# SCH_ECE198-04.net
KiCad netlist of a schematic drawn in EasyEDA
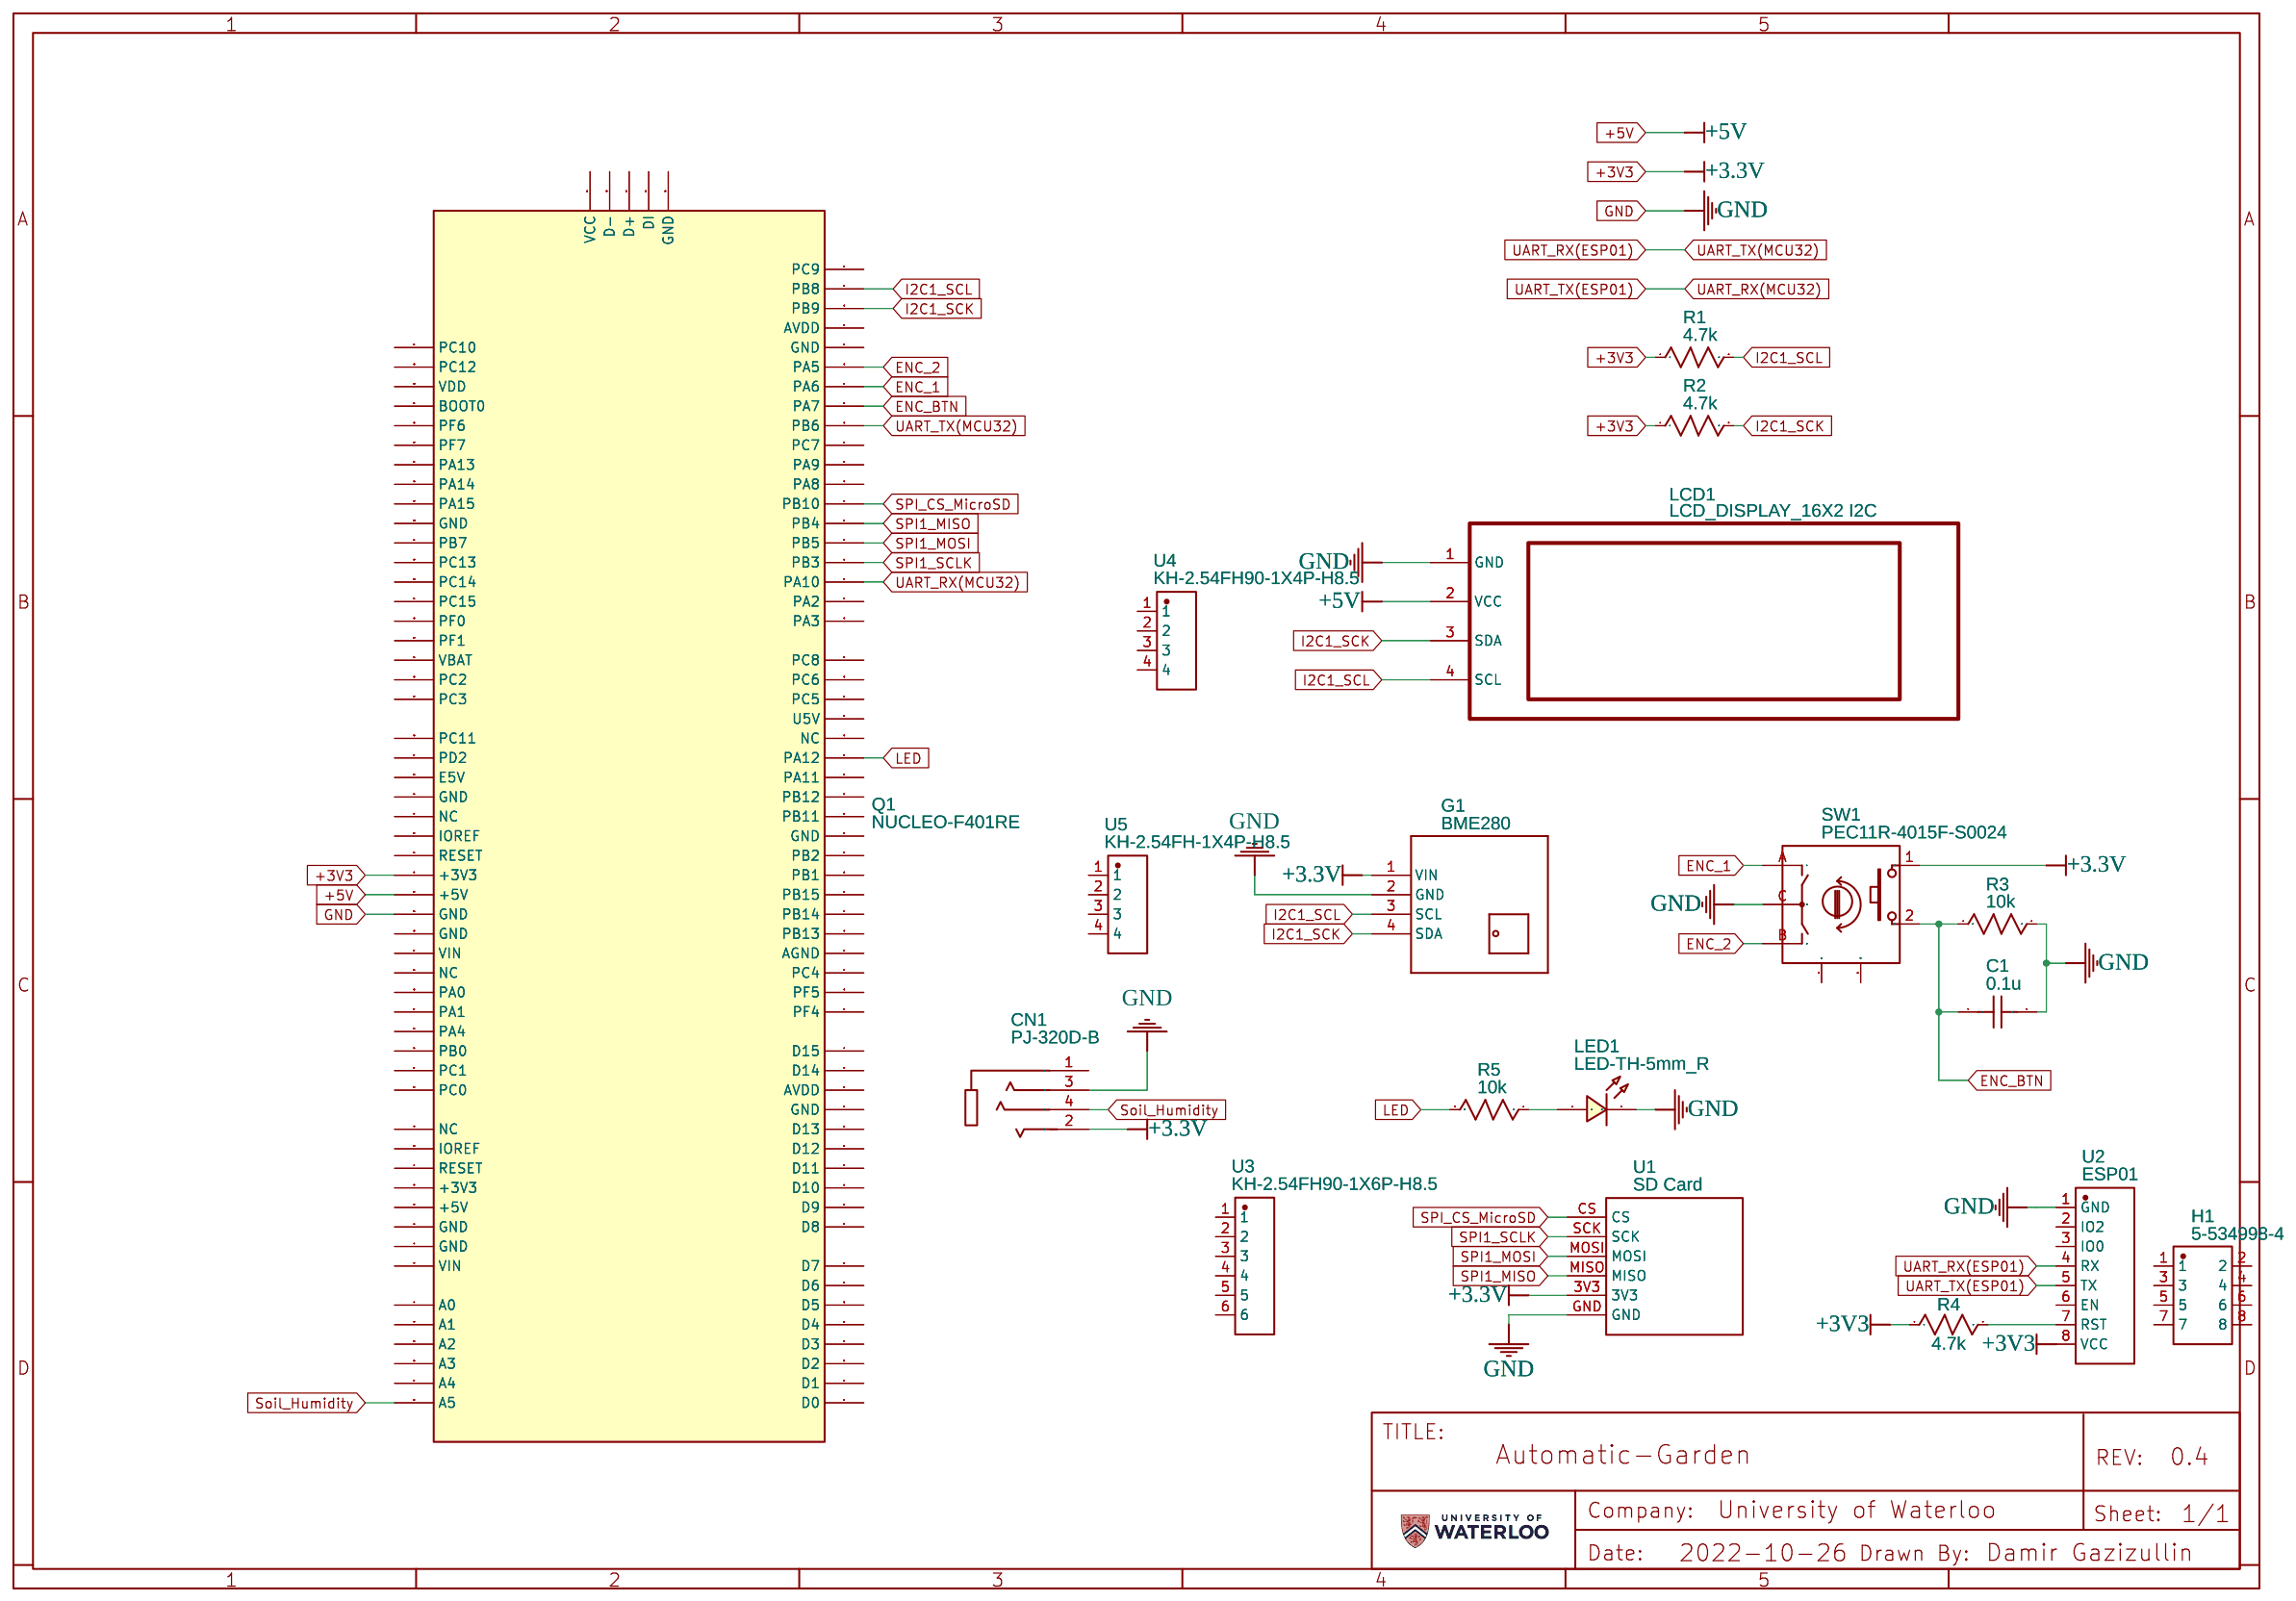
[diagram p0: schematic sheet]

(export (version "E")
  (design (tool "Eeschema 10.0.6"))
  (components
    (comp (ref "C1") (value "0.1u") (libsource (lib "") (part "C_0603_US")))
    (comp (ref "CN1")
      (value "PJ-320D-B")
      (fields (field (name "BOM_Supplier Part") "C2884940"))
      (libsource (lib "") (part "PJ-320D-B"))
    )
    (comp (ref "G1") (value "BME280") (libsource (lib "") (part "TEMP-HUM-PRES-BME280")))
    (comp (ref "H1")
      (value "5-534998-4")
      (fields (field (name "BOM_Supplier Part") "C404201"))
      (libsource (lib "") (part "5-534998-4"))
    )
    (comp (ref "LCD1") (value "LCD_DISPLAY_16X2 I2C") (libsource (lib "") (part "LCD_DISPLAY_16X2 I2C")))
    (comp (ref "LED1")
      (value "LED-TH-5mm_R")
      (fields
        (field (name "BOM_Manufacturer Part") "333-2SURD/S530-A3")
        (field (name "BOM_Supplier Part") "C87271")
      )
      (libsource (lib "") (part "LED-TH-5mm_R"))
    )
    (comp (ref "Q1") (value "NUCLEO-F401RE") (libsource (lib "") (part "NUCLEO-F401RE")))
    (comp (ref "R1") (value "4.7k") (libsource (lib "") (part "R_0603_US")))
    (comp (ref "R2") (value "4.7k") (libsource (lib "") (part "R_0603_US")))
    (comp (ref "R3") (value "10k") (libsource (lib "") (part "R_AXIAL-0.5_US")))
    (comp (ref "R4") (value "4.7k") (libsource (lib "") (part "R_AXIAL-0.5_US")))
    (comp (ref "R5") (value "10k") (libsource (lib "") (part "R_AXIAL-0.5_US_1")))
    (comp (ref "SW1")
      (value "PEC11R-4015F-S0024")
      (fields (field (name "BOM_Supplier Part") "C143789"))
      (libsource (lib "") (part "PEC11R-4015F-S0024"))
    )
    (comp (ref "U1") (value "SD Card") (libsource (lib "") (part "SD Card")))
    (comp (ref "U2") (value "ESP01") (libsource (lib "") (part "ESP01")))
    (comp (ref "U3")
      (value "KH-2.54FH90-1X6P-H8.5")
      (fields (field (name "BOM_Supplier Part") "C2932681"))
      (libsource (lib "") (part "KH-2.54FH90-1X6P-H8.5"))
    )
    (comp (ref "U4")
      (value "KH-2.54FH90-1X4P-H8.5")
      (fields (field (name "BOM_Supplier Part") "C2932680"))
      (libsource (lib "") (part "KH-2.54FH90-1X4P-H8.5"))
    )
    (comp (ref "U5")
      (value "KH-2.54FH-1X4P-H8.5")
      (fields (field (name "BOM_Supplier Part") "C2905415"))
      (libsource (lib "") (part "KH-2.54FH-1X4P-H8.5"))
    )
  )
  (nets
    (net (code "1") (name "+3V3") (class "Default")
      (node (ref "CN1") (pin "2") (pinfunction "2_2") (pintype "unspecified"))
      (node (ref "G1") (pin "1") (pinfunction "VIN_1") (pintype "bidirectional"))
      (node (ref "Q1") (pin "91") (pinfunction "+3V3_91") (pintype "unspecified"))
      (node (ref "R1") (pin "1") (pinfunction "1_1") (pintype "unspecified"))
      (node (ref "R2") (pin "1") (pinfunction "1_1") (pintype "unspecified"))
      (node (ref "R4") (pin "1") (pinfunction "1_1") (pintype "unspecified"))
      (node (ref "SW1") (pin "1") (pinfunction "1_1") (pintype "unspecified"))
      (node (ref "U1") (pin "3V3") (pinfunction "3V3_3V3") (pintype "unspecified"))
      (node (ref "U2") (pin "8") (pinfunction "VCC_8") (pintype "unspecified"))
    )
    (net (code "2") (name "+5V") (class "Default")
      (node (ref "LCD1") (pin "2") (pinfunction "VCC_2") (pintype "passive"))
      (node (ref "Q1") (pin "90") (pinfunction "+5V_90") (pintype "unspecified"))
    )
    (net (code "3") (name "ENC_1") (class "Default")
      (node (ref "Q1") (pin "14") (pinfunction "PA6_14") (pintype "bidirectional"))
      (node (ref "SW1") (pin "A") (pinfunction "A_A") (pintype "unspecified"))
    )
    (net (code "4") (name "ENC_2") (class "Default")
      (node (ref "Q1") (pin "13") (pinfunction "PA5_13") (pintype "bidirectional"))
      (node (ref "SW1") (pin "B") (pinfunction "B_B") (pintype "unspecified"))
    )
    (net (code "5") (name "ENC_BTN") (class "Default")
      (node (ref "C1") (pin "1") (pinfunction "1_1") (pintype "unspecified"))
      (node (ref "Q1") (pin "15") (pinfunction "PA7_15") (pintype "bidirectional"))
      (node (ref "R3") (pin "1") (pinfunction "1_1") (pintype "unspecified"))
      (node (ref "SW1") (pin "2") (pinfunction "2_2") (pintype "unspecified"))
    )
    (net (code "6") (name "GND") (class "Default")
      (node (ref "C1") (pin "2") (pinfunction "2_2") (pintype "unspecified"))
      (node (ref "CN1") (pin "3") (pinfunction "3_3") (pintype "unspecified"))
      (node (ref "G1") (pin "2") (pinfunction "GND_2") (pintype "bidirectional"))
      (node (ref "LCD1") (pin "1") (pinfunction "GND_1") (pintype "passive"))
      (node (ref "LED1") (pin "2") (pinfunction "2_2") (pintype "unspecified"))
      (node (ref "Q1") (pin "89") (pinfunction "GND_89") (pintype "unspecified"))
      (node (ref "R3") (pin "2") (pinfunction "2_2") (pintype "unspecified"))
      (node (ref "SW1") (pin "C") (pinfunction "C_C") (pintype "unspecified"))
      (node (ref "U1") (pin "GND") (pinfunction "GND_GND") (pintype "unspecified"))
      (node (ref "U2") (pin "1") (pinfunction "GND_1") (pintype "unspecified"))
    )
    (net (code "7") (name "I2C1_SCK") (class "Default")
      (node (ref "G1") (pin "4") (pinfunction "SDA_4") (pintype "bidirectional"))
      (node (ref "LCD1") (pin "3") (pinfunction "SDA_3") (pintype "passive"))
      (node (ref "Q1") (pin "10") (pinfunction "PB9_10") (pintype "bidirectional"))
      (node (ref "R2") (pin "2") (pinfunction "2_2") (pintype "unspecified"))
    )
    (net (code "8") (name "I2C1_SCL") (class "Default")
      (node (ref "G1") (pin "3") (pinfunction "SCL_3") (pintype "bidirectional"))
      (node (ref "LCD1") (pin "4") (pinfunction "SCL_4") (pintype "passive"))
      (node (ref "Q1") (pin "9") (pinfunction "PB8_9") (pintype "bidirectional"))
      (node (ref "R1") (pin "2") (pinfunction "2_2") (pintype "unspecified"))
    )
    (net (code "9") (name "LED") (class "Default")
      (node (ref "Q1") (pin "33") (pinfunction "PA12_33") (pintype "bidirectional"))
      (node (ref "R5") (pin "2") (pinfunction "2_2") (pintype "unspecified"))
    )
    (net (code "10") (name "Net-(LED1-Pad1)") (class "Default")
      (node (ref "LED1") (pin "1") (pinfunction "1_1") (pintype "unspecified"))
      (node (ref "R5") (pin "1") (pinfunction "1_1") (pintype "unspecified"))
    )
    (net (code "11") (name "Net-(U2-RST)") (class "Default")
      (node (ref "R4") (pin "2") (pinfunction "2_2") (pintype "unspecified"))
      (node (ref "U2") (pin "7") (pinfunction "RST_7") (pintype "unspecified"))
    )
    (net (code "12") (name "SPI1_MISO") (class "Default")
      (node (ref "Q1") (pin "21") (pinfunction "PB4_21") (pintype "bidirectional"))
      (node (ref "U1") (pin "MISO") (pinfunction "MISO_MISO") (pintype "unspecified"))
    )
    (net (code "13") (name "SPI1_MOSI") (class "Default")
      (node (ref "Q1") (pin "22") (pinfunction "PB5_22") (pintype "bidirectional"))
      (node (ref "U1") (pin "MOSI") (pinfunction "MOSI_MOSI") (pintype "unspecified"))
    )
    (net (code "14") (name "SPI1_SCLK") (class "Default")
      (node (ref "Q1") (pin "23") (pinfunction "PB3_23") (pintype "bidirectional"))
      (node (ref "U1") (pin "SCK") (pinfunction "SCK_SCK") (pintype "unspecified"))
    )
    (net (code "15") (name "SPI_CS_MicroSD") (class "Default")
      (node (ref "Q1") (pin "20") (pinfunction "PB10_20") (pintype "bidirectional"))
      (node (ref "U1") (pin "CS") (pinfunction "CS_CS") (pintype "unspecified"))
    )
    (net (code "16") (name "Soil_Humidity") (class "Default")
      (node (ref "CN1") (pin "4") (pinfunction "4_4") (pintype "unspecified"))
      (node (ref "Q1") (pin "66") (pinfunction "A5_66") (pintype "unspecified"))
    )
    (net (code "17") (name "UART_RX(ESP01)") (class "Default")
      (node (ref "Q1") (pin "16") (pinfunction "PB6_16") (pintype "bidirectional"))
      (node (ref "U2") (pin "4") (pinfunction "RX_4") (pintype "unspecified"))
    )
    (net (code "18") (name "UART_RX(MCU32)") (class "Default")
      (node (ref "Q1") (pin "24") (pinfunction "PA10_24") (pintype "bidirectional"))
      (node (ref "U2") (pin "5") (pinfunction "TX_5") (pintype "unspecified"))
    )
    (net (code "19") (name "unconnected-(CN1-Pad1)") (class "Default")
      (node (ref "CN1") (pin "1") (pinfunction "1_1") (pintype "unspecified"))
    )
    (net (code "20") (name "unconnected-(H1-Pad1)") (class "Default")
      (node (ref "H1") (pin "1") (pinfunction "1_1") (pintype "unspecified"))
    )
    (net (code "21") (name "unconnected-(H1-Pad2)") (class "Default")
      (node (ref "H1") (pin "2") (pinfunction "2_2") (pintype "unspecified"))
    )
    (net (code "22") (name "unconnected-(H1-Pad3)") (class "Default")
      (node (ref "H1") (pin "3") (pinfunction "3_3") (pintype "unspecified"))
    )
    (net (code "23") (name "unconnected-(H1-Pad4)") (class "Default")
      (node (ref "H1") (pin "4") (pinfunction "4_4") (pintype "unspecified"))
    )
    (net (code "24") (name "unconnected-(H1-Pad5)") (class "Default")
      (node (ref "H1") (pin "5") (pinfunction "5_5") (pintype "unspecified"))
    )
    (net (code "25") (name "unconnected-(H1-Pad6)") (class "Default")
      (node (ref "H1") (pin "6") (pinfunction "6_6") (pintype "unspecified"))
    )
    (net (code "26") (name "unconnected-(H1-Pad7)") (class "Default")
      (node (ref "H1") (pin "7") (pinfunction "7_7") (pintype "unspecified"))
    )
    (net (code "27") (name "unconnected-(H1-Pad8)") (class "Default")
      (node (ref "H1") (pin "8") (pinfunction "8_8") (pintype "unspecified"))
    )
    (net (code "28") (name "unconnected-(Q1-+3V3-Pad76)") (class "Default")
      (node (ref "Q1") (pin "76") (pinfunction "+3V3_76") (pintype "unspecified"))
    )
    (net (code "29") (name "unconnected-(Q1-+5V-Pad75)") (class "Default")
      (node (ref "Q1") (pin "75") (pinfunction "+5V_75") (pintype "unspecified"))
    )
    (net (code "30") (name "unconnected-(Q1-A0-Pad71)") (class "Default")
      (node (ref "Q1") (pin "71") (pinfunction "A0_71") (pintype "unspecified"))
    )
    (net (code "31") (name "unconnected-(Q1-A1-Pad70)") (class "Default")
      (node (ref "Q1") (pin "70") (pinfunction "A1_70") (pintype "unspecified"))
    )
    (net (code "32") (name "unconnected-(Q1-A2-Pad69)") (class "Default")
      (node (ref "Q1") (pin "69") (pinfunction "A2_69") (pintype "unspecified"))
    )
    (net (code "33") (name "unconnected-(Q1-A3-Pad68)") (class "Default")
      (node (ref "Q1") (pin "68") (pinfunction "A3_68") (pintype "unspecified"))
    )
    (net (code "34") (name "unconnected-(Q1-A4-Pad67)") (class "Default")
      (node (ref "Q1") (pin "67") (pinfunction "A4_67") (pintype "unspecified"))
    )
    (net (code "35") (name "unconnected-(Q1-AGND-Pad43)") (class "Default")
      (node (ref "Q1") (pin "43") (pinfunction "AGND_43") (pintype "unspecified"))
    )
    (net (code "36") (name "unconnected-(Q1-AVDD-Pad11)") (class "Default")
      (node (ref "Q1") (pin "11") (pinfunction "AVDD_11") (pintype "bidirectional"))
    )
    (net (code "37") (name "unconnected-(Q1-AVDD-Pad49)") (class "Default")
      (node (ref "Q1") (pin "49") (pinfunction "AVDD_49") (pintype "unspecified"))
    )
    (net (code "38") (name "unconnected-(Q1-BOOT0-Pad114)") (class "Default")
      (node (ref "Q1") (pin "114") (pinfunction "BOOT0_114") (pintype "unspecified"))
    )
    (net (code "39") (name "unconnected-(Q1-D+-Pad118)") (class "Default")
      (node (ref "Q1") (pin "118") (pinfunction "D+_118") (pintype "unspecified"))
    )
    (net (code "40") (name "unconnected-(Q1-D--Pad118)") (class "Default")
      (node (ref "Q1") (pin "118") (pinfunction "D-_118") (pintype "unspecified"))
    )
    (net (code "41") (name "unconnected-(Q1-D0-Pad65)") (class "Default")
      (node (ref "Q1") (pin "65") (pinfunction "D0_65") (pintype "unspecified"))
    )
    (net (code "42") (name "unconnected-(Q1-D1-Pad64)") (class "Default")
      (node (ref "Q1") (pin "64") (pinfunction "D1_64") (pintype "unspecified"))
    )
    (net (code "43") (name "unconnected-(Q1-D2-Pad63)") (class "Default")
      (node (ref "Q1") (pin "63") (pinfunction "D2_63") (pintype "unspecified"))
    )
    (net (code "44") (name "unconnected-(Q1-D3-Pad62)") (class "Default")
      (node (ref "Q1") (pin "62") (pinfunction "D3_62") (pintype "unspecified"))
    )
    (net (code "45") (name "unconnected-(Q1-D4-Pad61)") (class "Default")
      (node (ref "Q1") (pin "61") (pinfunction "D4_61") (pintype "unspecified"))
    )
    (net (code "46") (name "unconnected-(Q1-D5-Pad60)") (class "Default")
      (node (ref "Q1") (pin "60") (pinfunction "D5_60") (pintype "unspecified"))
    )
    (net (code "47") (name "unconnected-(Q1-D6-Pad59)") (class "Default")
      (node (ref "Q1") (pin "59") (pinfunction "D6_59") (pintype "unspecified"))
    )
    (net (code "48") (name "unconnected-(Q1-D7-Pad58)") (class "Default")
      (node (ref "Q1") (pin "58") (pinfunction "D7_58") (pintype "unspecified"))
    )
    (net (code "49") (name "unconnected-(Q1-D8-Pad56)") (class "Default")
      (node (ref "Q1") (pin "56") (pinfunction "D8_56") (pintype "unspecified"))
    )
    (net (code "50") (name "unconnected-(Q1-D9-Pad55)") (class "Default")
      (node (ref "Q1") (pin "55") (pinfunction "D9_55") (pintype "unspecified"))
    )
    (net (code "51") (name "unconnected-(Q1-D10-Pad54)") (class "Default")
      (node (ref "Q1") (pin "54") (pinfunction "D10_54") (pintype "unspecified"))
    )
    (net (code "52") (name "unconnected-(Q1-D11-Pad53)") (class "Default")
      (node (ref "Q1") (pin "53") (pinfunction "D11_53") (pintype "unspecified"))
    )
    (net (code "53") (name "unconnected-(Q1-D12-Pad52)") (class "Default")
      (node (ref "Q1") (pin "52") (pinfunction "D12_52") (pintype "unspecified"))
    )
    (net (code "54") (name "unconnected-(Q1-D13-Pad51)") (class "Default")
      (node (ref "Q1") (pin "51") (pinfunction "D13_51") (pintype "unspecified"))
    )
    (net (code "55") (name "unconnected-(Q1-D14-Pad48)") (class "Default")
      (node (ref "Q1") (pin "48") (pinfunction "D14_48") (pintype "unspecified"))
    )
    (net (code "56") (name "unconnected-(Q1-D15-Pad47)") (class "Default")
      (node (ref "Q1") (pin "47") (pinfunction "D15_47") (pintype "unspecified"))
    )
    (net (code "57") (name "unconnected-(Q1-DI-Pad118)") (class "Default")
      (node (ref "Q1") (pin "118") (pinfunction "DI_118") (pintype "unspecified"))
    )
    (net (code "58") (name "unconnected-(Q1-E5V-Pad96)") (class "Default")
      (node (ref "Q1") (pin "96") (pinfunction "E5V_96") (pintype "unspecified"))
    )
    (net (code "59") (name "unconnected-(Q1-GND-Pad12)") (class "Default")
      (node (ref "Q1") (pin "12") (pinfunction "GND_12") (pintype "bidirectional"))
    )
    (net (code "60") (name "unconnected-(Q1-GND-Pad37)") (class "Default")
      (node (ref "Q1") (pin "37") (pinfunction "GND_37") (pintype "unspecified"))
    )
    (net (code "61") (name "unconnected-(Q1-GND-Pad50)") (class "Default")
      (node (ref "Q1") (pin "50") (pinfunction "GND_50") (pintype "unspecified"))
    )
    (net (code "62") (name "unconnected-(Q1-GND-Pad73)") (class "Default")
      (node (ref "Q1") (pin "73") (pinfunction "GND_73") (pintype "unspecified"))
    )
    (net (code "63") (name "unconnected-(Q1-GND-Pad74)") (class "Default")
      (node (ref "Q1") (pin "74") (pinfunction "GND_74") (pintype "unspecified"))
    )
    (net (code "64") (name "unconnected-(Q1-GND-Pad88)") (class "Default")
      (node (ref "Q1") (pin "88") (pinfunction "GND_88") (pintype "unspecified"))
    )
    (net (code "65") (name "unconnected-(Q1-GND-Pad95)") (class "Default")
      (node (ref "Q1") (pin "95") (pinfunction "GND_95") (pintype "unspecified"))
    )
    (net (code "66") (name "unconnected-(Q1-GND-Pad108)") (class "Default")
      (node (ref "Q1") (pin "108") (pinfunction "GND_108") (pintype "unspecified"))
    )
    (net (code "67") (name "unconnected-(Q1-GND-Pad118)") (class "Default")
      (node (ref "Q1") (pin "118") (pinfunction "GND_118") (pintype "unspecified"))
    )
    (net (code "68") (name "unconnected-(Q1-IOREF-Pad78)") (class "Default")
      (node (ref "Q1") (pin "78") (pinfunction "IOREF_78") (pintype "unspecified"))
    )
    (net (code "69") (name "unconnected-(Q1-IOREF-Pad93)") (class "Default")
      (node (ref "Q1") (pin "93") (pinfunction "IOREF_93") (pintype "unspecified"))
    )
    (net (code "70") (name "unconnected-(Q1-NC-Pad32)") (class "Default")
      (node (ref "Q1") (pin "32") (pinfunction "NC_32") (pintype "bidirectional"))
    )
    (net (code "71") (name "unconnected-(Q1-NC-Pad79)") (class "Default")
      (node (ref "Q1") (pin "79") (pinfunction "NC_79") (pintype "unspecified"))
    )
    (net (code "72") (name "unconnected-(Q1-NC-Pad86)") (class "Default")
      (node (ref "Q1") (pin "86") (pinfunction "NC_86") (pintype "unspecified"))
    )
    (net (code "73") (name "unconnected-(Q1-NC-Pad94)") (class "Default")
      (node (ref "Q1") (pin "94") (pinfunction "NC_94") (pintype "unspecified"))
    )
    (net (code "74") (name "unconnected-(Q1-PA0-Pad85)") (class "Default")
      (node (ref "Q1") (pin "85") (pinfunction "PA0_85") (pintype "unspecified"))
    )
    (net (code "75") (name "unconnected-(Q1-PA1-Pad84)") (class "Default")
      (node (ref "Q1") (pin "84") (pinfunction "PA1_84") (pintype "unspecified"))
    )
    (net (code "76") (name "unconnected-(Q1-PA2-Pad25)") (class "Default")
      (node (ref "Q1") (pin "25") (pinfunction "PA2_25") (pintype "bidirectional"))
    )
    (net (code "77") (name "unconnected-(Q1-PA3-Pad26)") (class "Default")
      (node (ref "Q1") (pin "26") (pinfunction "PA3_26") (pintype "bidirectional"))
    )
    (net (code "78") (name "unconnected-(Q1-PA4-Pad83)") (class "Default")
      (node (ref "Q1") (pin "83") (pinfunction "PA4_83") (pintype "unspecified"))
    )
    (net (code "79") (name "unconnected-(Q1-PA8-Pad19)") (class "Default")
      (node (ref "Q1") (pin "19") (pinfunction "PA8_19") (pintype "bidirectional"))
    )
    (net (code "80") (name "unconnected-(Q1-PA9-Pad18)") (class "Default")
      (node (ref "Q1") (pin "18") (pinfunction "PA9_18") (pintype "bidirectional"))
    )
    (net (code "81") (name "unconnected-(Q1-PA11-Pad34)") (class "Default")
      (node (ref "Q1") (pin "34") (pinfunction "PA11_34") (pintype "bidirectional"))
    )
    (net (code "82") (name "unconnected-(Q1-PA13-Pad111)") (class "Default")
      (node (ref "Q1") (pin "111") (pinfunction "PA13_111") (pintype "unspecified"))
    )
    (net (code "83") (name "unconnected-(Q1-PA14-Pad110)") (class "Default")
      (node (ref "Q1") (pin "110") (pinfunction "PA14_110") (pintype "unspecified"))
    )
    (net (code "84") (name "unconnected-(Q1-PA15-Pad109)") (class "Default")
      (node (ref "Q1") (pin "109") (pinfunction "PA15_109") (pintype "unspecified"))
    )
    (net (code "85") (name "unconnected-(Q1-PB0-Pad82)") (class "Default")
      (node (ref "Q1") (pin "82") (pinfunction "PB0_82") (pintype "unspecified"))
    )
    (net (code "86") (name "unconnected-(Q1-PB1-Pad39)") (class "Default")
      (node (ref "Q1") (pin "39") (pinfunction "PB1_39") (pintype "unspecified"))
    )
    (net (code "87") (name "unconnected-(Q1-PB2-Pad38)") (class "Default")
      (node (ref "Q1") (pin "38") (pinfunction "PB2_38") (pintype "unspecified"))
    )
    (net (code "88") (name "unconnected-(Q1-PB7-Pad107)") (class "Default")
      (node (ref "Q1") (pin "107") (pinfunction "PB7_107") (pintype "unspecified"))
    )
    (net (code "89") (name "unconnected-(Q1-PB11-Pad36)") (class "Default")
      (node (ref "Q1") (pin "36") (pinfunction "PB11_36") (pintype "unspecified"))
    )
    (net (code "90") (name "unconnected-(Q1-PB12-Pad35)") (class "Default")
      (node (ref "Q1") (pin "35") (pinfunction "PB12_35") (pintype "unspecified"))
    )
    (net (code "91") (name "unconnected-(Q1-PB13-Pad42)") (class "Default")
      (node (ref "Q1") (pin "42") (pinfunction "PB13_42") (pintype "unspecified"))
    )
    (net (code "92") (name "unconnected-(Q1-PB14-Pad41)") (class "Default")
      (node (ref "Q1") (pin "41") (pinfunction "PB14_41") (pintype "unspecified"))
    )
    (net (code "93") (name "unconnected-(Q1-PB15-Pad40)") (class "Default")
      (node (ref "Q1") (pin "40") (pinfunction "PB15_40") (pintype "unspecified"))
    )
    (net (code "94") (name "unconnected-(Q1-PC0-Pad80)") (class "Default")
      (node (ref "Q1") (pin "80") (pinfunction "PC0_80") (pintype "unspecified"))
    )
    (net (code "95") (name "unconnected-(Q1-PC1-Pad81)") (class "Default")
      (node (ref "Q1") (pin "81") (pinfunction "PC1_81") (pintype "unspecified"))
    )
    (net (code "96") (name "unconnected-(Q1-PC2-Pad100)") (class "Default")
      (node (ref "Q1") (pin "100") (pinfunction "PC2_100") (pintype "unspecified"))
    )
    (net (code "97") (name "unconnected-(Q1-PC3-Pad99)") (class "Default")
      (node (ref "Q1") (pin "99") (pinfunction "PC3_99") (pintype "unspecified"))
    )
    (net (code "98") (name "unconnected-(Q1-PC4-Pad44)") (class "Default")
      (node (ref "Q1") (pin "44") (pinfunction "PC4_44") (pintype "unspecified"))
    )
    (net (code "99") (name "unconnected-(Q1-PC5-Pad30)") (class "Default")
      (node (ref "Q1") (pin "30") (pinfunction "PC5_30") (pintype "bidirectional"))
    )
    (net (code "100") (name "unconnected-(Q1-PC6-Pad29)") (class "Default")
      (node (ref "Q1") (pin "29") (pinfunction "PC6_29") (pintype "bidirectional"))
    )
    (net (code "101") (name "unconnected-(Q1-PC7-Pad17)") (class "Default")
      (node (ref "Q1") (pin "17") (pinfunction "PC7_17") (pintype "bidirectional"))
    )
    (net (code "102") (name "unconnected-(Q1-PC8-Pad28)") (class "Default")
      (node (ref "Q1") (pin "28") (pinfunction "PC8_28") (pintype "bidirectional"))
    )
    (net (code "103") (name "unconnected-(Q1-PC9-Pad8)") (class "Default")
      (node (ref "Q1") (pin "8") (pinfunction "PC9_8") (pintype "bidirectional"))
    )
    (net (code "104") (name "unconnected-(Q1-PC10-Pad117)") (class "Default")
      (node (ref "Q1") (pin "117") (pinfunction "PC10_117") (pintype "unspecified"))
    )
    (net (code "105") (name "unconnected-(Q1-PC11-Pad98)") (class "Default")
      (node (ref "Q1") (pin "98") (pinfunction "PC11_98") (pintype "unspecified"))
    )
    (net (code "106") (name "unconnected-(Q1-PC12-Pad116)") (class "Default")
      (node (ref "Q1") (pin "116") (pinfunction "PC12_116") (pintype "unspecified"))
    )
    (net (code "107") (name "unconnected-(Q1-PC13-Pad106)") (class "Default")
      (node (ref "Q1") (pin "106") (pinfunction "PC13_106") (pintype "unspecified"))
    )
    (net (code "108") (name "unconnected-(Q1-PC14-Pad105)") (class "Default")
      (node (ref "Q1") (pin "105") (pinfunction "PC14_105") (pintype "unspecified"))
    )
    (net (code "109") (name "unconnected-(Q1-PC15-Pad104)") (class "Default")
      (node (ref "Q1") (pin "104") (pinfunction "PC15_104") (pintype "unspecified"))
    )
    (net (code "110") (name "unconnected-(Q1-PD2-Pad97)") (class "Default")
      (node (ref "Q1") (pin "97") (pinfunction "PD2_97") (pintype "unspecified"))
    )
    (net (code "111") (name "unconnected-(Q1-PF0-Pad103)") (class "Default")
      (node (ref "Q1") (pin "103") (pinfunction "PF0_103") (pintype "unspecified"))
    )
    (net (code "112") (name "unconnected-(Q1-PF1-Pad102)") (class "Default")
      (node (ref "Q1") (pin "102") (pinfunction "PF1_102") (pintype "unspecified"))
    )
    (net (code "113") (name "unconnected-(Q1-PF4-Pad46)") (class "Default")
      (node (ref "Q1") (pin "46") (pinfunction "PF4_46") (pintype "unspecified"))
    )
    (net (code "114") (name "unconnected-(Q1-PF5-Pad45)") (class "Default")
      (node (ref "Q1") (pin "45") (pinfunction "PF5_45") (pintype "unspecified"))
    )
    (net (code "115") (name "unconnected-(Q1-PF6-Pad113)") (class "Default")
      (node (ref "Q1") (pin "113") (pinfunction "PF6_113") (pintype "unspecified"))
    )
    (net (code "116") (name "unconnected-(Q1-PF7-Pad112)") (class "Default")
      (node (ref "Q1") (pin "112") (pinfunction "PF7_112") (pintype "unspecified"))
    )
    (net (code "117") (name "unconnected-(Q1-RESET-Pad77)") (class "Default")
      (node (ref "Q1") (pin "77") (pinfunction "RESET_77") (pintype "unspecified"))
    )
    (net (code "118") (name "unconnected-(Q1-RESET-Pad92)") (class "Default")
      (node (ref "Q1") (pin "92") (pinfunction "RESET_92") (pintype "unspecified"))
    )
    (net (code "119") (name "unconnected-(Q1-U5V-Pad31)") (class "Default")
      (node (ref "Q1") (pin "31") (pinfunction "U5V_31") (pintype "bidirectional"))
    )
    (net (code "120") (name "unconnected-(Q1-VBAT-Pad101)") (class "Default")
      (node (ref "Q1") (pin "101") (pinfunction "VBAT_101") (pintype "unspecified"))
    )
    (net (code "121") (name "unconnected-(Q1-VCC-Pad118)") (class "Default")
      (node (ref "Q1") (pin "118") (pinfunction "VCC_118") (pintype "unspecified"))
    )
    (net (code "122") (name "unconnected-(Q1-VDD-Pad115)") (class "Default")
      (node (ref "Q1") (pin "115") (pinfunction "VDD_115") (pintype "unspecified"))
    )
    (net (code "123") (name "unconnected-(Q1-VIN-Pad72)") (class "Default")
      (node (ref "Q1") (pin "72") (pinfunction "VIN_72") (pintype "unspecified"))
    )
    (net (code "124") (name "unconnected-(Q1-VIN-Pad87)") (class "Default")
      (node (ref "Q1") (pin "87") (pinfunction "VIN_87") (pintype "unspecified"))
    )
    (net (code "125") (name "unconnected-(SW1-PadMT1)") (class "Default")
      (node (ref "SW1") (pin "MT1") (pinfunction "MT1_MT1") (pintype "unspecified"))
    )
    (net (code "126") (name "unconnected-(SW1-PadMT2)") (class "Default")
      (node (ref "SW1") (pin "MT2") (pinfunction "MT2_MT2") (pintype "unspecified"))
    )
    (net (code "127") (name "unconnected-(U2-EN-Pad6)") (class "Default")
      (node (ref "U2") (pin "6") (pinfunction "EN_6") (pintype "unspecified"))
    )
    (net (code "128") (name "unconnected-(U2-IO0-Pad3)") (class "Default")
      (node (ref "U2") (pin "3") (pinfunction "IO0_3") (pintype "unspecified"))
    )
    (net (code "129") (name "unconnected-(U2-IO2-Pad2)") (class "Default")
      (node (ref "U2") (pin "2") (pinfunction "IO2_2") (pintype "unspecified"))
    )
    (net (code "130") (name "unconnected-(U3-Pad1)") (class "Default")
      (node (ref "U3") (pin "1") (pinfunction "1_1") (pintype "unspecified"))
    )
    (net (code "131") (name "unconnected-(U3-Pad2)") (class "Default")
      (node (ref "U3") (pin "2") (pinfunction "2_2") (pintype "unspecified"))
    )
    (net (code "132") (name "unconnected-(U3-Pad3)") (class "Default")
      (node (ref "U3") (pin "3") (pinfunction "3_3") (pintype "unspecified"))
    )
    (net (code "133") (name "unconnected-(U3-Pad4)") (class "Default")
      (node (ref "U3") (pin "4") (pinfunction "4_4") (pintype "unspecified"))
    )
    (net (code "134") (name "unconnected-(U3-Pad5)") (class "Default")
      (node (ref "U3") (pin "5") (pinfunction "5_5") (pintype "unspecified"))
    )
    (net (code "135") (name "unconnected-(U3-Pad6)") (class "Default")
      (node (ref "U3") (pin "6") (pinfunction "6_6") (pintype "unspecified"))
    )
    (net (code "136") (name "unconnected-(U4-Pad1)") (class "Default")
      (node (ref "U4") (pin "1") (pinfunction "1_1") (pintype "unspecified"))
    )
    (net (code "137") (name "unconnected-(U4-Pad2)") (class "Default")
      (node (ref "U4") (pin "2") (pinfunction "2_2") (pintype "unspecified"))
    )
    (net (code "138") (name "unconnected-(U4-Pad3)") (class "Default")
      (node (ref "U4") (pin "3") (pinfunction "3_3") (pintype "unspecified"))
    )
    (net (code "139") (name "unconnected-(U4-Pad4)") (class "Default")
      (node (ref "U4") (pin "4") (pinfunction "4_4") (pintype "unspecified"))
    )
    (net (code "140") (name "unconnected-(U5-Pad1)") (class "Default")
      (node (ref "U5") (pin "1") (pinfunction "1_1") (pintype "unspecified"))
    )
    (net (code "141") (name "unconnected-(U5-Pad2)") (class "Default")
      (node (ref "U5") (pin "2") (pinfunction "2_2") (pintype "unspecified"))
    )
    (net (code "142") (name "unconnected-(U5-Pad3)") (class "Default")
      (node (ref "U5") (pin "3") (pinfunction "3_3") (pintype "unspecified"))
    )
    (net (code "143") (name "unconnected-(U5-Pad4)") (class "Default")
      (node (ref "U5") (pin "4") (pinfunction "4_4") (pintype "unspecified"))
    )
  )
)
